# rbroce_schematic.net
KiCad netlist of a schematic drawn in EAGLE
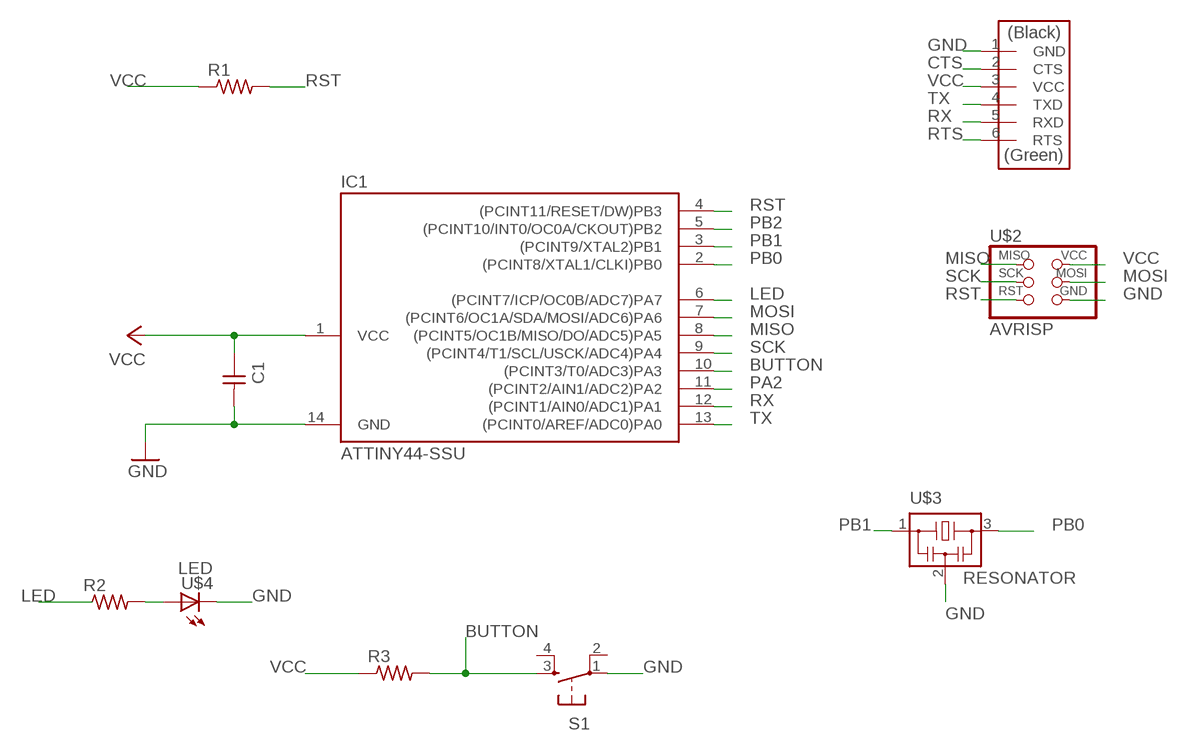
[diagram p0: schematic, sheet 1]

(export (version "E")
  (design (tool "Eeschema 10.0.6"))
  (components
    (comp (ref "C1")
      (value "CAP-UNPOLARIZED")
      (footprint "eagle-import:C1206")
      (libsource (lib "eagle-import") (part "CAP-UNPOLARIZED"))
    )
    (comp (ref "IC1")
      (value "ATTINY44-SSU")
      (footprint "eagle-import:SOIC14")
      (libsource (lib "eagle-import") (part "ATTINY44-SSU"))
    )
    (comp (ref "R1")
      (value "RES-US1206FAB")
      (footprint "eagle-import:R1206FAB")
      (libsource (lib "eagle-import") (part "RES-US1206FAB"))
    )
    (comp (ref "R2")
      (value "RES-US1206")
      (footprint "eagle-import:R1206")
      (libsource (lib "eagle-import") (part "RES-US1206"))
    )
    (comp (ref "R3")
      (value "RES-US1206")
      (footprint "eagle-import:R1206")
      (libsource (lib "eagle-import") (part "RES-US1206"))
    )
    (comp (ref "S1")
      (value "6MM_SWITCH6MM_SWITCH")
      (footprint "eagle-import:6MM_SWITCH")
      (libsource (lib "eagle-import") (part "6MM_SWITCH6MM_SWITCH"))
    )
    (comp (ref "U$1")
      (value "FTDI-SMD-HEADER")
      (footprint "eagle-import:1X06SMD")
      (libsource (lib "eagle-import") (part "FTDI-SMD-HEADER"))
    )
    (comp (ref "U$2")
      (value "AVRISP")
      (footprint "eagle-import:2X03")
      (libsource (lib "eagle-import") (part "AVRISP"))
    )
    (comp (ref "U$3")
      (value "RESONATOR")
      (footprint "eagle-import:EFOBM")
      (libsource (lib "eagle-import") (part "RESONATOR"))
    )
    (comp (ref "U$4")
      (value "LED")
      (footprint "eagle-import:LED1206")
      (libsource (lib "eagle-import") (part "LED"))
    )
  )
  (nets
    (net (code "1") (name "/BUTTON") (class "Default")
      (node (ref "IC1") (pin "10") (pinfunction "(PCINT3/T0/ADC3)PA3_10") (pintype "bidirectional"))
      (node (ref "R3") (pin "2") (pinfunction "2_2") (pintype "passive"))
      (node (ref "S1") (pin "3") (pinfunction "S_3") (pintype "passive"))
    )
    (net (code "2") (name "/CTS") (class "Default")
      (node (ref "U$1") (pin "2") (pinfunction "CTS_2") (pintype "bidirectional"))
    )
    (net (code "3") (name "/LED") (class "Default")
      (node (ref "IC1") (pin "6") (pinfunction "(PCINT7/ICP/OC0B/ADC7)PA7_6") (pintype "bidirectional"))
      (node (ref "R2") (pin "1") (pinfunction "1_1") (pintype "passive"))
    )
    (net (code "4") (name "/MISO") (class "Default")
      (node (ref "IC1") (pin "8") (pinfunction "(PCINT5/OC1B/MISO/DO/ADC5)PA5_8") (pintype "bidirectional"))
      (node (ref "U$2") (pin "1") (pinfunction "MISO_1") (pintype "passive"))
    )
    (net (code "5") (name "/MOSI") (class "Default")
      (node (ref "IC1") (pin "7") (pinfunction "(PCINT6/OC1A/SDA/MOSI/ADC6)PA6_7") (pintype "bidirectional"))
      (node (ref "U$2") (pin "4") (pinfunction "MOSI_4") (pintype "passive"))
    )
    (net (code "6") (name "/PA2") (class "Default")
      (node (ref "IC1") (pin "11") (pinfunction "(PCINT2/AIN1/ADC2)PA2_11") (pintype "bidirectional"))
    )
    (net (code "7") (name "/PB0") (class "Default")
      (node (ref "IC1") (pin "2") (pinfunction "(PCINT8/XTAL1/CLKI)PB0_2") (pintype "bidirectional"))
      (node (ref "U$3") (pin "3") (pinfunction "3_3") (pintype "passive"))
    )
    (net (code "8") (name "/PB1") (class "Default")
      (node (ref "IC1") (pin "3") (pinfunction "(PCINT9/XTAL2)PB1_3") (pintype "bidirectional"))
      (node (ref "U$3") (pin "1") (pinfunction "1_1") (pintype "passive"))
    )
    (net (code "9") (name "/PB2") (class "Default")
      (node (ref "IC1") (pin "5") (pinfunction "(PCINT10/INT0/OC0A/CKOUT)PB2_5") (pintype "bidirectional"))
    )
    (net (code "10") (name "/RST") (class "Default")
      (node (ref "IC1") (pin "4") (pinfunction "(PCINT11/RESET/DW)PB3_4") (pintype "bidirectional"))
      (node (ref "R1") (pin "2") (pinfunction "2_2") (pintype "passive"))
      (node (ref "U$2") (pin "5") (pinfunction "RST_5") (pintype "passive"))
    )
    (net (code "11") (name "/RTS") (class "Default")
      (node (ref "U$1") (pin "6") (pinfunction "RTS_6") (pintype "bidirectional"))
    )
    (net (code "12") (name "/RX") (class "Default")
      (node (ref "IC1") (pin "12") (pinfunction "(PCINT1/AIN0/ADC1)PA1_12") (pintype "bidirectional"))
      (node (ref "U$1") (pin "5") (pinfunction "RXD_5") (pintype "bidirectional"))
    )
    (net (code "13") (name "/SCK") (class "Default")
      (node (ref "IC1") (pin "9") (pinfunction "(PCINT4/T1/SCL/USCK/ADC4)PA4_9") (pintype "bidirectional"))
      (node (ref "U$2") (pin "3") (pinfunction "SCK_3") (pintype "passive"))
    )
    (net (code "14") (name "/TX") (class "Default")
      (node (ref "IC1") (pin "13") (pinfunction "(PCINT0/AREF/ADC0)PA0_13") (pintype "bidirectional"))
      (node (ref "U$1") (pin "4") (pinfunction "TXD_4") (pintype "bidirectional"))
    )
    (net (code "15") (name "GND") (class "Default")
      (node (ref "C1") (pin "2") (pinfunction "2_2") (pintype "passive"))
      (node (ref "IC1") (pin "14") (pinfunction "GND_14") (pintype "power_in"))
      (node (ref "S1") (pin "1") (pinfunction "P_1") (pintype "passive"))
      (node (ref "U$1") (pin "1") (pinfunction "GND_1") (pintype "bidirectional"))
      (node (ref "U$2") (pin "6") (pinfunction "GND_6") (pintype "passive"))
      (node (ref "U$3") (pin "2") (pinfunction "2_2") (pintype "passive"))
      (node (ref "U$4") (pin "2") (pinfunction "C_2") (pintype "passive"))
    )
    (net (code "16") (name "Net-(U$4-A)") (class "Default")
      (node (ref "R2") (pin "2") (pinfunction "2_2") (pintype "passive"))
      (node (ref "U$4") (pin "1") (pinfunction "A_1") (pintype "passive"))
    )
    (net (code "17") (name "VCC") (class "Default")
      (node (ref "C1") (pin "1") (pinfunction "1_1") (pintype "passive"))
      (node (ref "IC1") (pin "1") (pinfunction "VCC_1") (pintype "power_in"))
      (node (ref "R1") (pin "1") (pinfunction "1_1") (pintype "passive"))
      (node (ref "R3") (pin "1") (pinfunction "1_1") (pintype "passive"))
      (node (ref "U$1") (pin "3") (pinfunction "VCC_3") (pintype "bidirectional"))
      (node (ref "U$2") (pin "2") (pinfunction "VCC_2") (pintype "passive"))
    )
    (net (code "18") (name "unconnected-(S1-P1-Pad2)") (class "Default")
      (node (ref "S1") (pin "2") (pinfunction "P1_2") (pintype "passive"))
    )
    (net (code "19") (name "unconnected-(S1-S1-Pad4)") (class "Default")
      (node (ref "S1") (pin "4") (pinfunction "S1_4") (pintype "passive"))
    )
  )
)
